# MRDT0001A1.net
KiCad netlist of a schematic drawn in EAGLE
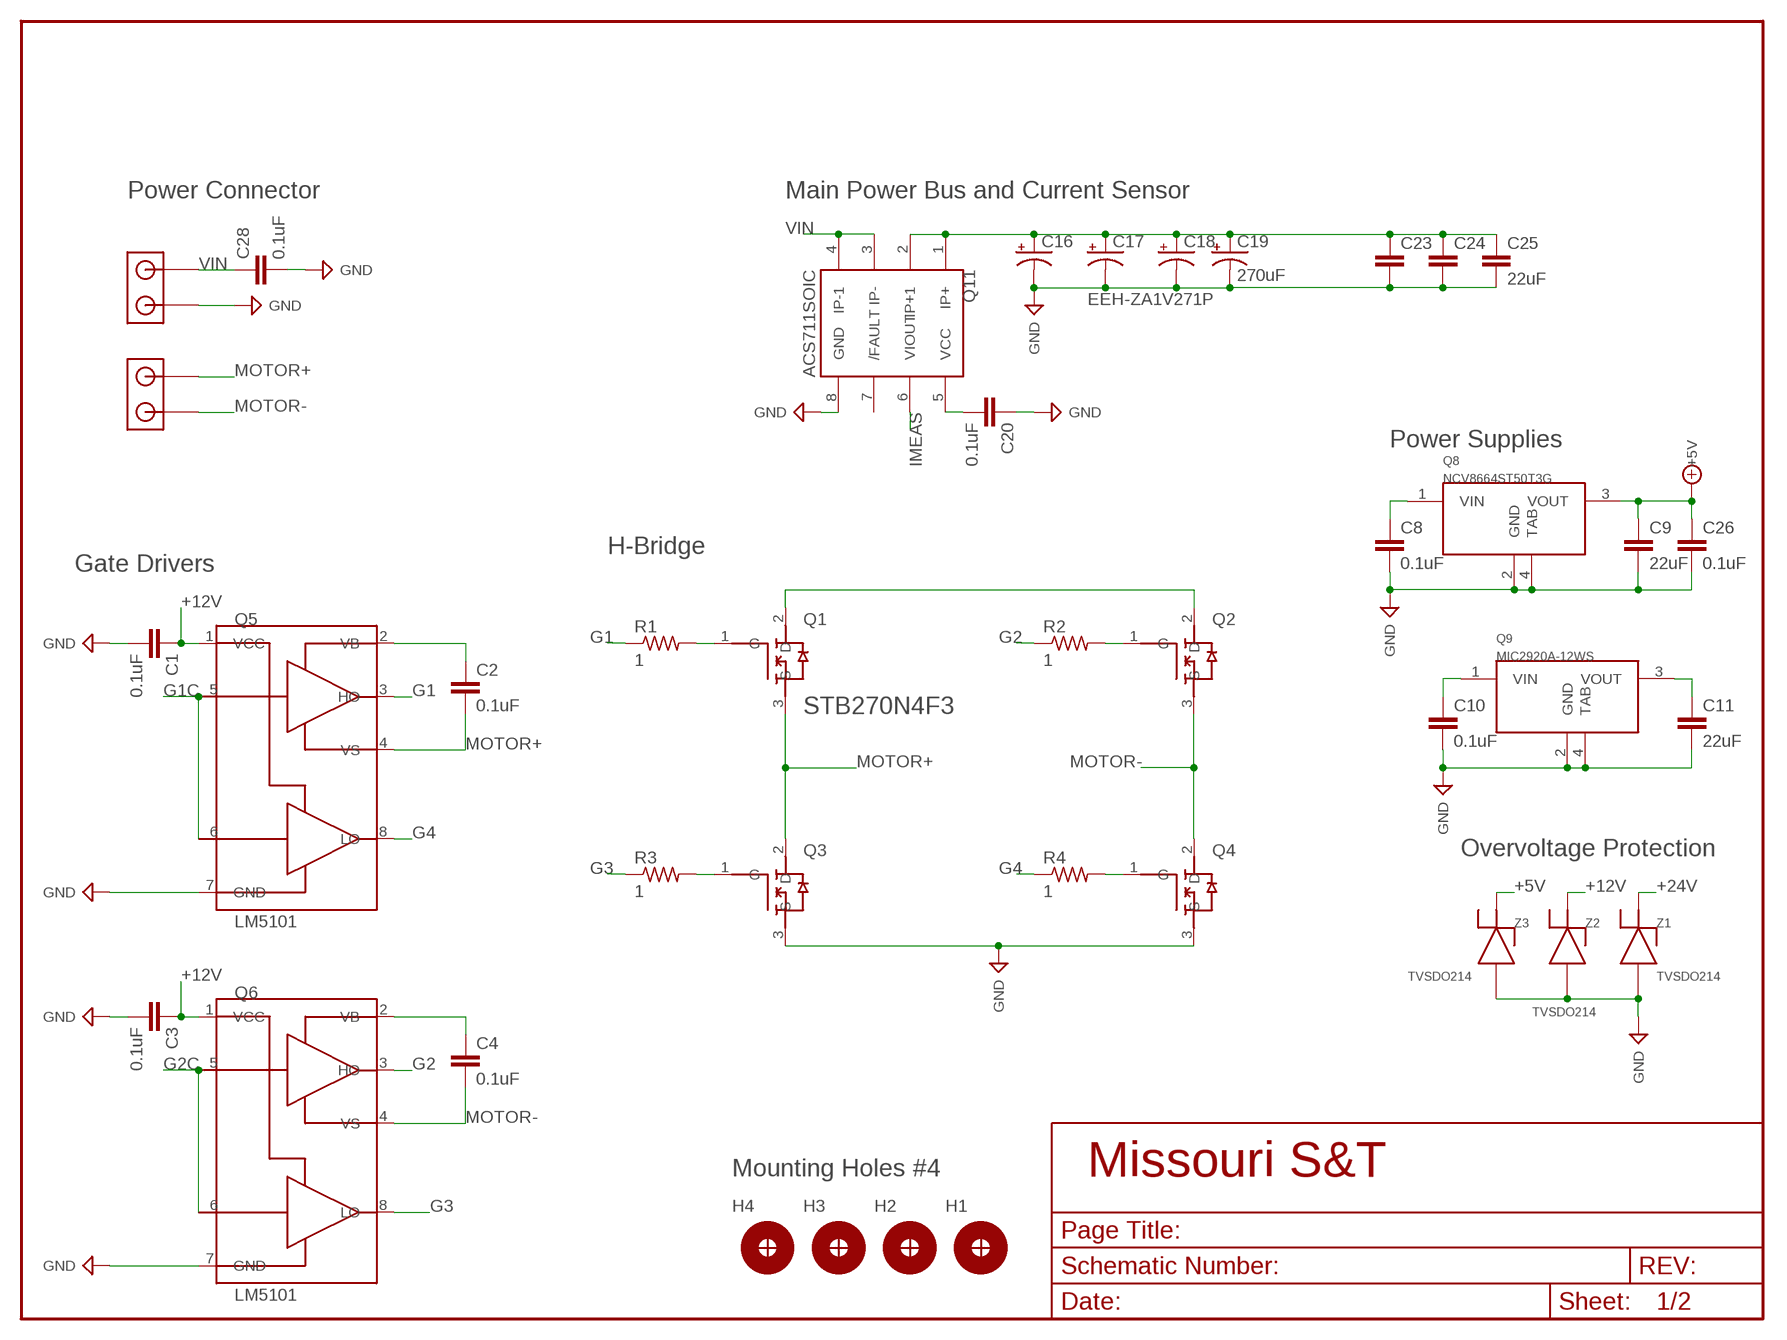
[diagram p0: schematic, sheet 1]
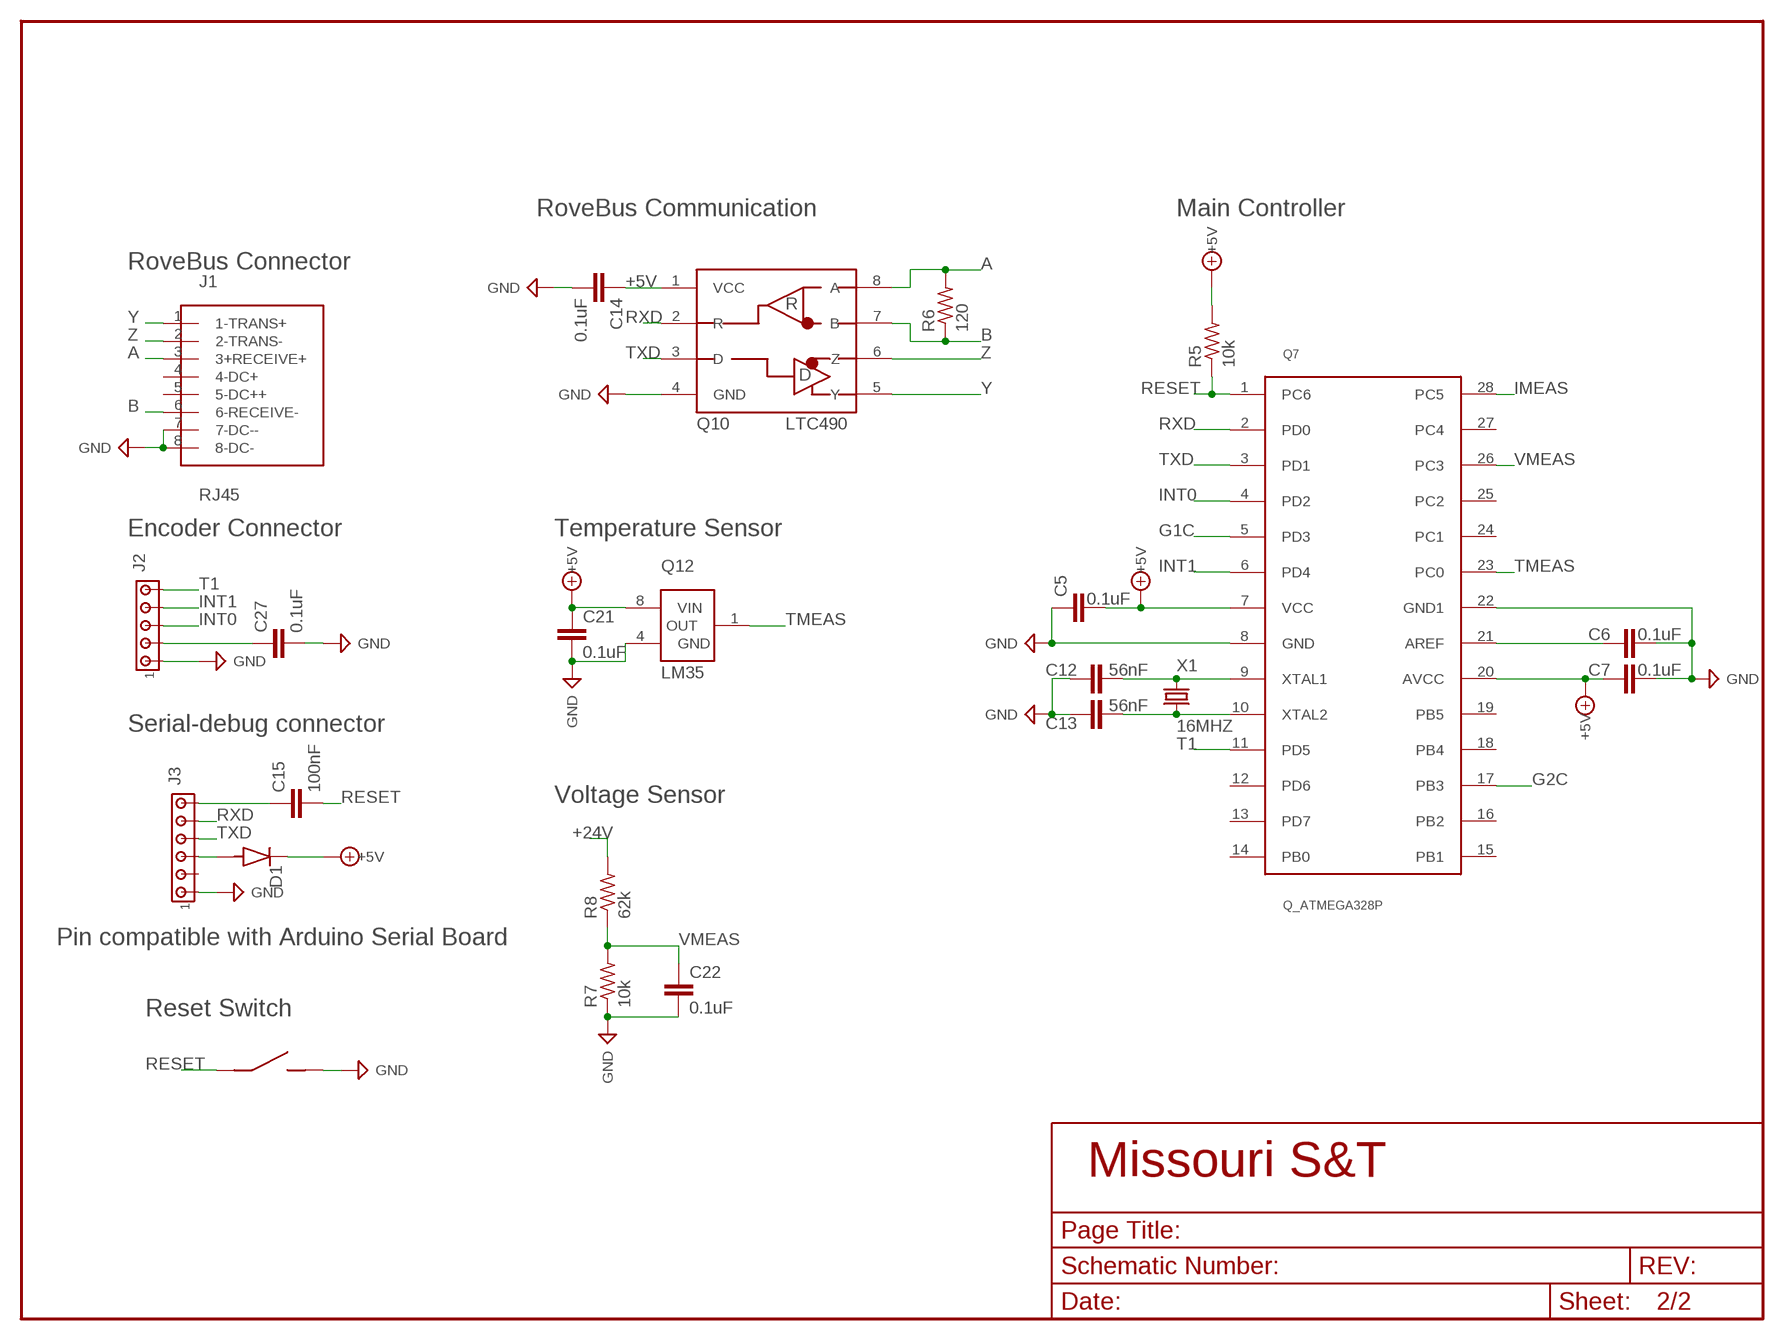
[diagram p1: schematic, sheet 2]

(export (version "E")
  (design (tool "Eeschema 10.0.6"))
  (components
    (comp (ref "C5")
      (value "0.1uF")
      (footprint "eagle-import:C_0805")
      (libsource (lib "eagle-import") (part "Master_C_CAP_0805"))
    )
    (comp (ref "C6")
      (value "0.1uF")
      (footprint "eagle-import:C_0805")
      (libsource (lib "eagle-import") (part "Master_C_CAP_0805"))
    )
    (comp (ref "C7")
      (value "0.1uF")
      (footprint "eagle-import:C_0805")
      (libsource (lib "eagle-import") (part "Master_C_CAP_0805"))
    )
    (comp (ref "C12")
      (value "56nF")
      (footprint "eagle-import:C_1206")
      (libsource (lib "eagle-import") (part "Master_C_CAP_1206"))
    )
    (comp (ref "C13")
      (value "56nF")
      (footprint "eagle-import:C_1206")
      (libsource (lib "eagle-import") (part "Master_C_CAP_1206"))
    )
    (comp (ref "C14")
      (value "0.1uF")
      (footprint "eagle-import:C_0805")
      (libsource (lib "eagle-import") (part "Master_C_CAP_0805"))
    )
    (comp (ref "C15")
      (value "100nF")
      (footprint "eagle-import:C_0805")
      (libsource (lib "eagle-import") (part "Master_C_CAP_0805"))
    )
    (comp (ref "C21")
      (value "0.1uF")
      (footprint "eagle-import:C_0805")
      (libsource (lib "eagle-import") (part "Master_C_CAP_0805"))
    )
    (comp (ref "C22")
      (value "0.1uF")
      (footprint "eagle-import:C_0805")
      (libsource (lib "eagle-import") (part "Master_C_CAP_0805"))
    )
    (comp (ref "C27")
      (value "0.1uF")
      (footprint "eagle-import:C_0805")
      (libsource (lib "eagle-import") (part "Master_C_CAP_0805"))
    )
    (comp (ref "D1")
      (value "D_DIODEDO214AC")
      (footprint "eagle-import:DO-214AC")
      (libsource (lib "eagle-import") (part "D_DIODEDO214AC"))
    )
    (comp (ref "J1")
      (value "RJ45")
      (footprint "eagle-import:RJ45-CAT5E")
      (libsource (lib "eagle-import") (part "RJ45"))
    )
    (comp (ref "J2")
      (value "J_MTA5P_100")
      (footprint "eagle-import:J_MTA100_5P")
      (libsource (lib "eagle-import") (part "J_MTA5P_100"))
    )
    (comp (ref "J3")
      (value "J_MTA6P_100")
      (footprint "eagle-import:J_MTA100_6P")
      (libsource (lib "eagle-import") (part "J_MTA6P_100"))
    )
    (comp (ref "J6")
      (value "J_MC32857")
      (footprint "eagle-import:J_TOGGLE")
      (libsource (lib "eagle-import") (part "J_MC32857"))
    )
    (comp (ref "Q7")
      (value "Q_ATMEGA328P")
      (footprint "eagle-import:DIP28")
      (libsource (lib "eagle-import") (part "Q_ATMEGA328P"))
    )
    (comp (ref "Q10")
      (value "LTC490")
      (footprint "eagle-import:SOIC8")
      (libsource (lib "eagle-import") (part "RS485FULL"))
    )
    (comp (ref "Q12")
      (value "LM35")
      (footprint "eagle-import:SOIC8")
      (libsource (lib "eagle-import") (part "Q_LM35SOIC8"))
    )
    (comp (ref "R5")
      (value "10k")
      (footprint "eagle-import:R_0805")
      (libsource (lib "eagle-import") (part "R_RES_0805"))
    )
    (comp (ref "R6")
      (value "120")
      (footprint "eagle-import:R_0805")
      (libsource (lib "eagle-import") (part "R_RES_0805"))
    )
    (comp (ref "R7")
      (value "10k")
      (footprint "eagle-import:R_0805")
      (libsource (lib "eagle-import") (part "R_RES_0805"))
    )
    (comp (ref "R8")
      (value "62k")
      (footprint "eagle-import:R_0805")
      (libsource (lib "eagle-import") (part "R_RES_0805"))
    )
    (comp (ref "X1")
      (value "16MHZ")
      (footprint "eagle-import:HC-49")
      (libsource (lib "eagle-import") (part "X_HC49SCRYSTALTH"))
    )
    (comp (ref "C1")
      (value "0.1uF")
      (footprint "eagle-import:C_0805")
      (libsource (lib "eagle-import") (part "Master_C_CAP_0805"))
    )
    (comp (ref "C2")
      (value "0.1uF")
      (footprint "eagle-import:C_1206")
      (libsource (lib "eagle-import") (part "Master_C_CAP_1206"))
    )
    (comp (ref "C3")
      (value "0.1uF")
      (footprint "eagle-import:C_0805")
      (libsource (lib "eagle-import") (part "Master_C_CAP_0805"))
    )
    (comp (ref "C4")
      (value "0.1uF")
      (footprint "eagle-import:C_1206")
      (libsource (lib "eagle-import") (part "Master_C_CAP_1206"))
    )
    (comp (ref "C8")
      (value "0.1uF")
      (footprint "eagle-import:C_1206")
      (libsource (lib "eagle-import") (part "Master_C_CAP_1206"))
    )
    (comp (ref "C9")
      (value "22uF")
      (footprint "eagle-import:C_1206")
      (libsource (lib "eagle-import") (part "Master_C_CAP_1206"))
    )
    (comp (ref "C10")
      (value "0.1uF")
      (footprint "eagle-import:C_1206")
      (libsource (lib "eagle-import") (part "Master_C_CAP_1206"))
    )
    (comp (ref "C11")
      (value "22uF")
      (footprint "eagle-import:C_1206")
      (libsource (lib "eagle-import") (part "Master_C_CAP_1206"))
    )
    (comp (ref "C16")
      (value "CAP_POL10MMSM")
      (footprint "eagle-import:C_10MMSM")
      (libsource (lib "eagle-import") (part "CAP_POL10MMSM"))
    )
    (comp (ref "C17")
      (value "CAP_POL10MMSM")
      (footprint "eagle-import:C_10MMSM")
      (libsource (lib "eagle-import") (part "CAP_POL10MMSM"))
    )
    (comp (ref "C18")
      (value "CAP_POL10MMSM")
      (footprint "eagle-import:C_10MMSM")
      (libsource (lib "eagle-import") (part "CAP_POL10MMSM"))
    )
    (comp (ref "C19")
      (value "270uF")
      (footprint "eagle-import:C_10MMSM")
      (libsource (lib "eagle-import") (part "CAP_POL10MMSM"))
    )
    (comp (ref "C20")
      (value "0.1uF")
      (footprint "eagle-import:C_1206")
      (libsource (lib "eagle-import") (part "Master_C_CAP_1206"))
    )
    (comp (ref "C23")
      (value "C_CAP_1206")
      (footprint "eagle-import:C_1206")
      (libsource (lib "eagle-import") (part "C_CAP_1206"))
    )
    (comp (ref "C24")
      (value "C_CAP_1206")
      (footprint "eagle-import:C_1206")
      (libsource (lib "eagle-import") (part "C_CAP_1206"))
    )
    (comp (ref "C25")
      (value "22uF")
      (footprint "eagle-import:C_1206")
      (libsource (lib "eagle-import") (part "C_CAP_1206"))
    )
    (comp (ref "C26")
      (value "0.1uF")
      (footprint "eagle-import:C_1206")
      (libsource (lib "eagle-import") (part "Master_C_CAP_1206"))
    )
    (comp (ref "C28")
      (value "0.1uF")
      (footprint "eagle-import:C_0805")
      (libsource (lib "eagle-import") (part "Master_C_CAP_0805"))
    )
    (comp (ref "H1")
      (value "H_MNTHOLE_#4")
      (footprint "eagle-import:H_MNTHOLE_#4")
      (libsource (lib "eagle-import") (part "H_MNTHOLE_#4"))
    )
    (comp (ref "H2")
      (value "H_MNTHOLE_#4")
      (footprint "eagle-import:H_MNTHOLE_#4")
      (libsource (lib "eagle-import") (part "H_MNTHOLE_#4"))
    )
    (comp (ref "H3")
      (value "H_MNTHOLE_#4")
      (footprint "eagle-import:H_MNTHOLE_#4")
      (libsource (lib "eagle-import") (part "H_MNTHOLE_#4"))
    )
    (comp (ref "H4")
      (value "H_MNTHOLE_#4")
      (footprint "eagle-import:H_MNTHOLE_#4")
      (libsource (lib "eagle-import") (part "H_MNTHOLE_#4"))
    )
    (comp (ref "J4")
      (value "J_1546074-2")
      (footprint "eagle-import:THERM_BLOCK_2")
      (libsource (lib "eagle-import") (part "J_1546074-2"))
    )
    (comp (ref "J5")
      (value "J_1546074-2")
      (footprint "eagle-import:THERM_BLOCK_2")
      (libsource (lib "eagle-import") (part "J_1546074-2"))
    )
    (comp (ref "Q1")
      (value "N-CH-MOSFETTO263")
      (footprint "eagle-import:TO-263")
      (libsource (lib "eagle-import") (part "N-CH-MOSFETTO263"))
    )
    (comp (ref "Q2")
      (value "N-CH-MOSFETTO263")
      (footprint "eagle-import:TO-263")
      (libsource (lib "eagle-import") (part "N-CH-MOSFETTO263"))
    )
    (comp (ref "Q3")
      (value "N-CH-MOSFETTO263")
      (footprint "eagle-import:TO-263")
      (libsource (lib "eagle-import") (part "N-CH-MOSFETTO263"))
    )
    (comp (ref "Q4")
      (value "N-CH-MOSFETTO263")
      (footprint "eagle-import:TO-263")
      (libsource (lib "eagle-import") (part "N-CH-MOSFETTO263"))
    )
    (comp (ref "Q5")
      (value "LM5101")
      (footprint "eagle-import:SOIC8")
      (libsource (lib "eagle-import") (part "LM5101SOIC8"))
    )
    (comp (ref "Q6")
      (value "LM5101")
      (footprint "eagle-import:SOIC8")
      (libsource (lib "eagle-import") (part "LM5101SOIC8"))
    )
    (comp (ref "Q8")
      (value "NCV8664ST50T3G")
      (footprint "eagle-import:SOT-223")
      (libsource (lib "eagle-import") (part "LDO-4PINSOT223"))
    )
    (comp (ref "Q9")
      (value "MIC2920A-12WS")
      (footprint "eagle-import:SOT-223")
      (libsource (lib "eagle-import") (part "LDO-4PINSOT223"))
    )
    (comp (ref "Q11")
      (value "ACS711SOIC")
      (footprint "eagle-import:SOIC8")
      (libsource (lib "eagle-import") (part "ACS711SOIC"))
    )
    (comp (ref "R1")
      (value "1")
      (footprint "eagle-import:R_0805")
      (libsource (lib "eagle-import") (part "R_RES_0805"))
    )
    (comp (ref "R2")
      (value "1")
      (footprint "eagle-import:R_0805")
      (libsource (lib "eagle-import") (part "R_RES_0805"))
    )
    (comp (ref "R3")
      (value "1")
      (footprint "eagle-import:R_0805")
      (libsource (lib "eagle-import") (part "R_RES_0805"))
    )
    (comp (ref "R4")
      (value "1")
      (footprint "eagle-import:R_0805")
      (libsource (lib "eagle-import") (part "R_RES_0805"))
    )
    (comp (ref "Z1")
      (value "TVSDO214")
      (footprint "eagle-import:DO-214AC")
      (libsource (lib "eagle-import") (part "Z_TVSDO214"))
    )
    (comp (ref "Z2")
      (value "TVSDO214")
      (footprint "eagle-import:DO-214AC")
      (libsource (lib "eagle-import") (part "Z_TVSDO214"))
    )
    (comp (ref "Z3")
      (value "TVSDO214")
      (footprint "eagle-import:DO-214AC")
      (libsource (lib "eagle-import") (part "Z_TVSDO214"))
    )
  )
  (nets
    (net (code "1") (name "+5V") (class "Default")
      (node (ref "C14") (pin "1") (pinfunction "1_1") (pintype "passive"))
      (node (ref "C21") (pin "1") (pinfunction "1_1") (pintype "passive"))
      (node (ref "C26") (pin "1") (pinfunction "1_1") (pintype "passive"))
      (node (ref "C27") (pin "1") (pinfunction "1_1") (pintype "passive"))
      (node (ref "C5") (pin "2") (pinfunction "2_2") (pintype "passive"))
      (node (ref "C7") (pin "1") (pinfunction "1_1") (pintype "passive"))
      (node (ref "C9") (pin "1") (pinfunction "1_1") (pintype "passive"))
      (node (ref "D1") (pin "C") (pinfunction "C_C") (pintype "bidirectional"))
      (node (ref "J2") (pin "2") (pinfunction "2_2") (pintype "passive"))
      (node (ref "Q10") (pin "1") (pinfunction "VCC_1") (pintype "bidirectional"))
      (node (ref "Q12") (pin "8") (pinfunction "VIN_8") (pintype "bidirectional"))
      (node (ref "Q7") (pin "20") (pinfunction "AVCC_20") (pintype "bidirectional"))
      (node (ref "Q7") (pin "7") (pinfunction "VCC_7") (pintype "bidirectional"))
      (node (ref "Q8") (pin "3") (pinfunction "VOUT_3") (pintype "bidirectional"))
      (node (ref "R5") (pin "2") (pinfunction "2_2") (pintype "passive"))
      (node (ref "Z3") (pin "C") (pinfunction "C_C") (pintype "bidirectional"))
    )
    (net (code "2") (name "+12V") (class "Default")
      (node (ref "C1") (pin "1") (pinfunction "1_1") (pintype "passive"))
      (node (ref "C11") (pin "1") (pinfunction "1_1") (pintype "passive"))
      (node (ref "C3") (pin "1") (pinfunction "1_1") (pintype "passive"))
      (node (ref "Q5") (pin "1") (pinfunction "VCC_1") (pintype "bidirectional"))
      (node (ref "Q6") (pin "1") (pinfunction "VCC_1") (pintype "bidirectional"))
      (node (ref "Q9") (pin "3") (pinfunction "VOUT_3") (pintype "bidirectional"))
      (node (ref "Z2") (pin "C") (pinfunction "C_C") (pintype "bidirectional"))
    )
    (net (code "3") (name "+24V") (class "Default")
      (node (ref "C10") (pin "1") (pinfunction "1_1") (pintype "passive"))
      (node (ref "C16") (pin "+") (pinfunction "+_+") (pintype "passive"))
      (node (ref "C17") (pin "+") (pinfunction "+_+") (pintype "passive"))
      (node (ref "C18") (pin "+") (pinfunction "+_+") (pintype "passive"))
      (node (ref "C19") (pin "+") (pinfunction "+_+") (pintype "passive"))
      (node (ref "C23") (pin "1") (pinfunction "1_1") (pintype "passive"))
      (node (ref "C24") (pin "1") (pinfunction "1_1") (pintype "passive"))
      (node (ref "C25") (pin "1") (pinfunction "1_1") (pintype "passive"))
      (node (ref "Q1") (pin "2") (pinfunction "D_2") (pintype "bidirectional"))
      (node (ref "Q11") (pin "1") (pinfunction "IP+_1") (pintype "bidirectional"))
      (node (ref "Q11") (pin "2") (pinfunction "IP+1_2") (pintype "bidirectional"))
      (node (ref "Q2") (pin "2") (pinfunction "D_2") (pintype "bidirectional"))
      (node (ref "Q9") (pin "1") (pinfunction "VIN_1") (pintype "bidirectional"))
      (node (ref "R8") (pin "2") (pinfunction "2_2") (pintype "passive"))
      (node (ref "Z1") (pin "C") (pinfunction "C_C") (pintype "bidirectional"))
    )
    (net (code "4") (name "A") (class "Default")
      (node (ref "J1") (pin "3") (pinfunction "3+RECEIVE+_3") (pintype "bidirectional"))
      (node (ref "Q10") (pin "8") (pinfunction "A_8") (pintype "bidirectional"))
      (node (ref "R6") (pin "2") (pinfunction "2_2") (pintype "passive"))
    )
    (net (code "5") (name "B") (class "Default")
      (node (ref "J1") (pin "6") (pinfunction "6-RECEIVE-_6") (pintype "bidirectional"))
      (node (ref "Q10") (pin "7") (pinfunction "B_7") (pintype "bidirectional"))
      (node (ref "R6") (pin "1") (pinfunction "1_1") (pintype "passive"))
    )
    (net (code "6") (name "G1") (class "Default")
      (node (ref "Q5") (pin "3") (pinfunction "HO_3") (pintype "bidirectional"))
      (node (ref "R1") (pin "1") (pinfunction "1_1") (pintype "passive"))
    )
    (net (code "7") (name "G1C") (class "Default")
      (node (ref "Q5") (pin "5") (pinfunction "HI_5") (pintype "bidirectional"))
      (node (ref "Q5") (pin "6") (pinfunction "LI_6") (pintype "bidirectional"))
      (node (ref "Q7") (pin "5") (pinfunction "PD3_5") (pintype "bidirectional"))
    )
    (net (code "8") (name "G2") (class "Default")
      (node (ref "Q6") (pin "3") (pinfunction "HO_3") (pintype "bidirectional"))
      (node (ref "R2") (pin "1") (pinfunction "1_1") (pintype "passive"))
    )
    (net (code "9") (name "G2C") (class "Default")
      (node (ref "Q6") (pin "5") (pinfunction "HI_5") (pintype "bidirectional"))
      (node (ref "Q6") (pin "6") (pinfunction "LI_6") (pintype "bidirectional"))
      (node (ref "Q7") (pin "17") (pinfunction "PB3_17") (pintype "bidirectional"))
    )
    (net (code "10") (name "G3") (class "Default")
      (node (ref "Q6") (pin "8") (pinfunction "LO_8") (pintype "bidirectional"))
      (node (ref "R3") (pin "1") (pinfunction "1_1") (pintype "passive"))
    )
    (net (code "11") (name "G4") (class "Default")
      (node (ref "Q5") (pin "8") (pinfunction "LO_8") (pintype "bidirectional"))
      (node (ref "R4") (pin "1") (pinfunction "1_1") (pintype "passive"))
    )
    (net (code "12") (name "GND") (class "Default")
      (node (ref "C1") (pin "2") (pinfunction "2_2") (pintype "passive"))
      (node (ref "C10") (pin "2") (pinfunction "2_2") (pintype "passive"))
      (node (ref "C11") (pin "2") (pinfunction "2_2") (pintype "passive"))
      (node (ref "C12") (pin "1") (pinfunction "1_1") (pintype "passive"))
      (node (ref "C13") (pin "1") (pinfunction "1_1") (pintype "passive"))
      (node (ref "C14") (pin "2") (pinfunction "2_2") (pintype "passive"))
      (node (ref "C16") (pin "-") (pinfunction "-_-") (pintype "passive"))
      (node (ref "C17") (pin "-") (pinfunction "-_-") (pintype "passive"))
      (node (ref "C18") (pin "-") (pinfunction "-_-") (pintype "passive"))
      (node (ref "C19") (pin "-") (pinfunction "-_-") (pintype "passive"))
      (node (ref "C20") (pin "1") (pinfunction "1_1") (pintype "passive"))
      (node (ref "C21") (pin "2") (pinfunction "2_2") (pintype "passive"))
      (node (ref "C22") (pin "2") (pinfunction "2_2") (pintype "passive"))
      (node (ref "C23") (pin "2") (pinfunction "2_2") (pintype "passive"))
      (node (ref "C24") (pin "2") (pinfunction "2_2") (pintype "passive"))
      (node (ref "C25") (pin "2") (pinfunction "2_2") (pintype "passive"))
      (node (ref "C26") (pin "2") (pinfunction "2_2") (pintype "passive"))
      (node (ref "C27") (pin "2") (pinfunction "2_2") (pintype "passive"))
      (node (ref "C28") (pin "2") (pinfunction "2_2") (pintype "passive"))
      (node (ref "C3") (pin "2") (pinfunction "2_2") (pintype "passive"))
      (node (ref "C5") (pin "1") (pinfunction "1_1") (pintype "passive"))
      (node (ref "C6") (pin "2") (pinfunction "2_2") (pintype "passive"))
      (node (ref "C7") (pin "2") (pinfunction "2_2") (pintype "passive"))
      (node (ref "C8") (pin "2") (pinfunction "2_2") (pintype "passive"))
      (node (ref "C9") (pin "2") (pinfunction "2_2") (pintype "passive"))
      (node (ref "J1") (pin "7") (pinfunction "7-DC--_7") (pintype "bidirectional"))
      (node (ref "J1") (pin "8") (pinfunction "8-DC-_8") (pintype "bidirectional"))
      (node (ref "J2") (pin "1") (pinfunction "1_1") (pintype "passive"))
      (node (ref "J3") (pin "1") (pinfunction "1_1") (pintype "passive"))
      (node (ref "J4") (pin "P$1") (pinfunction "P$1_P$1") (pintype "bidirectional"))
      (node (ref "J6") (pin "P$2") (pinfunction "2_P$2") (pintype "bidirectional"))
      (node (ref "Q10") (pin "4") (pinfunction "GND_4") (pintype "bidirectional"))
      (node (ref "Q11") (pin "8") (pinfunction "GND_8") (pintype "bidirectional"))
      (node (ref "Q12") (pin "4") (pinfunction "GND_4") (pintype "bidirectional"))
      (node (ref "Q3") (pin "3") (pinfunction "S_3") (pintype "bidirectional"))
      (node (ref "Q4") (pin "3") (pinfunction "S_3") (pintype "bidirectional"))
      (node (ref "Q5") (pin "7") (pinfunction "GND_7") (pintype "bidirectional"))
      (node (ref "Q6") (pin "7") (pinfunction "GND_7") (pintype "bidirectional"))
      (node (ref "Q7") (pin "22") (pinfunction "GND1_22") (pintype "bidirectional"))
      (node (ref "Q7") (pin "8") (pinfunction "GND_8") (pintype "bidirectional"))
      (node (ref "Q8") (pin "2") (pinfunction "GND_2") (pintype "bidirectional"))
      (node (ref "Q8") (pin "4") (pinfunction "TAB_4") (pintype "bidirectional"))
      (node (ref "Q9") (pin "2") (pinfunction "GND_2") (pintype "bidirectional"))
      (node (ref "Q9") (pin "4") (pinfunction "TAB_4") (pintype "bidirectional"))
      (node (ref "R7") (pin "1") (pinfunction "1_1") (pintype "passive"))
      (node (ref "Z1") (pin "A") (pinfunction "A_A") (pintype "bidirectional"))
      (node (ref "Z2") (pin "A") (pinfunction "A_A") (pintype "bidirectional"))
      (node (ref "Z3") (pin "A") (pinfunction "A_A") (pintype "bidirectional"))
    )
    (net (code "13") (name "IMEAS") (class "Default")
      (node (ref "Q11") (pin "6") (pinfunction "VIOUT_6") (pintype "bidirectional"))
      (node (ref "Q7") (pin "28") (pinfunction "PC5_28") (pintype "bidirectional"))
    )
    (net (code "14") (name "INT0") (class "Default")
      (node (ref "J2") (pin "3") (pinfunction "3_3") (pintype "passive"))
      (node (ref "Q7") (pin "4") (pinfunction "PD2_4") (pintype "bidirectional"))
    )
    (net (code "15") (name "INT1") (class "Default")
      (node (ref "J2") (pin "4") (pinfunction "4_4") (pintype "passive"))
      (node (ref "Q7") (pin "6") (pinfunction "PD4_6") (pintype "bidirectional"))
    )
    (net (code "16") (name "MOTOR+") (class "Default")
      (node (ref "C2") (pin "2") (pinfunction "2_2") (pintype "passive"))
      (node (ref "J5") (pin "P$2") (pinfunction "P$2_P$2") (pintype "bidirectional"))
      (node (ref "Q1") (pin "3") (pinfunction "S_3") (pintype "bidirectional"))
      (node (ref "Q3") (pin "2") (pinfunction "D_2") (pintype "bidirectional"))
      (node (ref "Q5") (pin "4") (pinfunction "VS_4") (pintype "bidirectional"))
    )
    (net (code "17") (name "MOTOR-") (class "Default")
      (node (ref "C4") (pin "2") (pinfunction "2_2") (pintype "passive"))
      (node (ref "J5") (pin "P$1") (pinfunction "P$1_P$1") (pintype "bidirectional"))
      (node (ref "Q2") (pin "3") (pinfunction "S_3") (pintype "bidirectional"))
      (node (ref "Q4") (pin "2") (pinfunction "D_2") (pintype "bidirectional"))
      (node (ref "Q6") (pin "4") (pinfunction "VS_4") (pintype "bidirectional"))
    )
    (net (code "18") (name "Net-(C15-Pad1)") (class "Default")
      (node (ref "C15") (pin "1") (pinfunction "1_1") (pintype "passive"))
      (node (ref "J3") (pin "6") (pinfunction "6_6") (pintype "passive"))
    )
    (net (code "19") (name "Net-(D1-PadA)") (class "Default")
      (node (ref "D1") (pin "A") (pinfunction "A_A") (pintype "bidirectional"))
      (node (ref "J3") (pin "3") (pinfunction "3_3") (pintype "passive"))
    )
    (net (code "20") (name "Net-(Q1-G)") (class "Default")
      (node (ref "Q1") (pin "1") (pinfunction "G_1") (pintype "bidirectional"))
      (node (ref "R1") (pin "2") (pinfunction "2_2") (pintype "passive"))
    )
    (net (code "21") (name "Net-(Q2-G)") (class "Default")
      (node (ref "Q2") (pin "1") (pinfunction "G_1") (pintype "bidirectional"))
      (node (ref "R2") (pin "2") (pinfunction "2_2") (pintype "passive"))
    )
    (net (code "22") (name "Net-(Q3-G)") (class "Default")
      (node (ref "Q3") (pin "1") (pinfunction "G_1") (pintype "bidirectional"))
      (node (ref "R3") (pin "2") (pinfunction "2_2") (pintype "passive"))
    )
    (net (code "23") (name "Net-(Q4-G)") (class "Default")
      (node (ref "Q4") (pin "1") (pinfunction "G_1") (pintype "bidirectional"))
      (node (ref "R4") (pin "2") (pinfunction "2_2") (pintype "passive"))
    )
    (net (code "24") (name "Net-(Q5-VB)") (class "Default")
      (node (ref "C2") (pin "1") (pinfunction "1_1") (pintype "passive"))
      (node (ref "Q5") (pin "2") (pinfunction "VB_2") (pintype "bidirectional"))
    )
    (net (code "25") (name "Net-(Q6-VB)") (class "Default")
      (node (ref "C4") (pin "1") (pinfunction "1_1") (pintype "passive"))
      (node (ref "Q6") (pin "2") (pinfunction "VB_2") (pintype "bidirectional"))
    )
    (net (code "26") (name "Net-(Q7-AREF)") (class "Default")
      (node (ref "C6") (pin "1") (pinfunction "1_1") (pintype "passive"))
      (node (ref "Q7") (pin "21") (pinfunction "AREF_21") (pintype "bidirectional"))
    )
    (net (code "27") (name "Net-(Q7-XTAL1)") (class "Default")
      (node (ref "C12") (pin "2") (pinfunction "2_2") (pintype "passive"))
      (node (ref "Q7") (pin "9") (pinfunction "XTAL1_9") (pintype "bidirectional"))
      (node (ref "X1") (pin "P$1") (pinfunction "1_P$1") (pintype "passive"))
    )
    (net (code "28") (name "Net-(Q7-XTAL2)") (class "Default")
      (node (ref "C13") (pin "2") (pinfunction "2_2") (pintype "passive"))
      (node (ref "Q7") (pin "10") (pinfunction "XTAL2_10") (pintype "bidirectional"))
      (node (ref "X1") (pin "P$2") (pinfunction "2_P$2") (pintype "passive"))
    )
    (net (code "29") (name "Net-(Q11-VCC)") (class "Default")
      (node (ref "C20") (pin "2") (pinfunction "2_2") (pintype "passive"))
      (node (ref "Q11") (pin "5") (pinfunction "VCC_5") (pintype "bidirectional"))
    )
    (net (code "30") (name "RESET") (class "Default")
      (node (ref "C15") (pin "2") (pinfunction "2_2") (pintype "passive"))
      (node (ref "J6") (pin "P$1") (pinfunction "1_P$1") (pintype "bidirectional"))
      (node (ref "Q7") (pin "1") (pinfunction "PC6_1") (pintype "bidirectional"))
      (node (ref "R5") (pin "1") (pinfunction "1_1") (pintype "passive"))
    )
    (net (code "31") (name "RXD") (class "Default")
      (node (ref "J3") (pin "5") (pinfunction "5_5") (pintype "passive"))
      (node (ref "Q10") (pin "2") (pinfunction "R_2") (pintype "bidirectional"))
      (node (ref "Q7") (pin "2") (pinfunction "PD0_2") (pintype "bidirectional"))
    )
    (net (code "32") (name "T1") (class "Default")
      (node (ref "J2") (pin "5") (pinfunction "5_5") (pintype "passive"))
      (node (ref "Q7") (pin "11") (pinfunction "PD5_11") (pintype "bidirectional"))
    )
    (net (code "33") (name "TMEAS") (class "Default")
      (node (ref "Q12") (pin "1") (pinfunction "OUT_1") (pintype "bidirectional"))
      (node (ref "Q7") (pin "23") (pinfunction "PC0_23") (pintype "bidirectional"))
    )
    (net (code "34") (name "TXD") (class "Default")
      (node (ref "J3") (pin "4") (pinfunction "4_4") (pintype "passive"))
      (node (ref "Q10") (pin "3") (pinfunction "D_3") (pintype "bidirectional"))
      (node (ref "Q7") (pin "3") (pinfunction "PD1_3") (pintype "bidirectional"))
    )
    (net (code "35") (name "VIN") (class "Default")
      (node (ref "C28") (pin "1") (pinfunction "1_1") (pintype "passive"))
      (node (ref "C8") (pin "1") (pinfunction "1_1") (pintype "passive"))
      (node (ref "J4") (pin "P$2") (pinfunction "P$2_P$2") (pintype "bidirectional"))
      (node (ref "Q11") (pin "3") (pinfunction "IP-_3") (pintype "bidirectional"))
      (node (ref "Q11") (pin "4") (pinfunction "IP-1_4") (pintype "bidirectional"))
      (node (ref "Q8") (pin "1") (pinfunction "VIN_1") (pintype "bidirectional"))
    )
    (net (code "36") (name "VMEAS") (class "Default")
      (node (ref "C22") (pin "1") (pinfunction "1_1") (pintype "passive"))
      (node (ref "Q7") (pin "26") (pinfunction "PC3_26") (pintype "bidirectional"))
      (node (ref "R7") (pin "2") (pinfunction "2_2") (pintype "passive"))
      (node (ref "R8") (pin "1") (pinfunction "1_1") (pintype "passive"))
    )
    (net (code "37") (name "Y") (class "Default")
      (node (ref "J1") (pin "1") (pinfunction "1-TRANS+_1") (pintype "bidirectional"))
      (node (ref "Q10") (pin "5") (pinfunction "Y_5") (pintype "bidirectional"))
    )
    (net (code "38") (name "Z") (class "Default")
      (node (ref "J1") (pin "2") (pinfunction "2-TRANS-_2") (pintype "bidirectional"))
      (node (ref "Q10") (pin "6") (pinfunction "Z_6") (pintype "bidirectional"))
    )
    (net (code "39") (name "unconnected-(H1-Pad1)") (class "Default")
      (node (ref "H1") (pin "1") (pinfunction "1_1") (pintype "passive"))
    )
    (net (code "40") (name "unconnected-(H2-Pad1)") (class "Default")
      (node (ref "H2") (pin "1") (pinfunction "1_1") (pintype "passive"))
    )
    (net (code "41") (name "unconnected-(H3-Pad1)") (class "Default")
      (node (ref "H3") (pin "1") (pinfunction "1_1") (pintype "passive"))
    )
    (net (code "42") (name "unconnected-(H4-Pad1)") (class "Default")
      (node (ref "H4") (pin "1") (pinfunction "1_1") (pintype "passive"))
    )
    (net (code "43") (name "unconnected-(J1-4-DC+-Pad4)") (class "Default")
      (node (ref "J1") (pin "4") (pinfunction "4-DC+_4") (pintype "bidirectional"))
    )
    (net (code "44") (name "unconnected-(J1-5-DC++-Pad5)") (class "Default")
      (node (ref "J1") (pin "5") (pinfunction "5-DC++_5") (pintype "bidirectional"))
    )
    (net (code "45") (name "unconnected-(J3-Pad2)") (class "Default")
      (node (ref "J3") (pin "2") (pinfunction "2_2") (pintype "passive"))
    )
    (net (code "46") (name "unconnected-(Q7-PB0-Pad14)") (class "Default")
      (node (ref "Q7") (pin "14") (pinfunction "PB0_14") (pintype "bidirectional"))
    )
    (net (code "47") (name "unconnected-(Q7-PB1-Pad15)") (class "Default")
      (node (ref "Q7") (pin "15") (pinfunction "PB1_15") (pintype "bidirectional"))
    )
    (net (code "48") (name "unconnected-(Q7-PB2-Pad16)") (class "Default")
      (node (ref "Q7") (pin "16") (pinfunction "PB2_16") (pintype "bidirectional"))
    )
    (net (code "49") (name "unconnected-(Q7-PB4-Pad18)") (class "Default")
      (node (ref "Q7") (pin "18") (pinfunction "PB4_18") (pintype "bidirectional"))
    )
    (net (code "50") (name "unconnected-(Q7-PB5-Pad19)") (class "Default")
      (node (ref "Q7") (pin "19") (pinfunction "PB5_19") (pintype "bidirectional"))
    )
    (net (code "51") (name "unconnected-(Q7-PC1-Pad24)") (class "Default")
      (node (ref "Q7") (pin "24") (pinfunction "PC1_24") (pintype "bidirectional"))
    )
    (net (code "52") (name "unconnected-(Q7-PC2-Pad25)") (class "Default")
      (node (ref "Q7") (pin "25") (pinfunction "PC2_25") (pintype "bidirectional"))
    )
    (net (code "53") (name "unconnected-(Q7-PC4-Pad27)") (class "Default")
      (node (ref "Q7") (pin "27") (pinfunction "PC4_27") (pintype "bidirectional"))
    )
    (net (code "54") (name "unconnected-(Q7-PD6-Pad12)") (class "Default")
      (node (ref "Q7") (pin "12") (pinfunction "PD6_12") (pintype "bidirectional"))
    )
    (net (code "55") (name "unconnected-(Q7-PD7-Pad13)") (class "Default")
      (node (ref "Q7") (pin "13") (pinfunction "PD7_13") (pintype "bidirectional"))
    )
    (net (code "56") (name "unconnected-(Q11-{slash}FAULT-Pad7)") (class "Default")
      (node (ref "Q11") (pin "7") (pinfunction "/FAULT_7") (pintype "bidirectional"))
    )
  )
)
